# rpi-cc2652p-uart.net
KiCad netlist of a schematic drawn in EAGLE
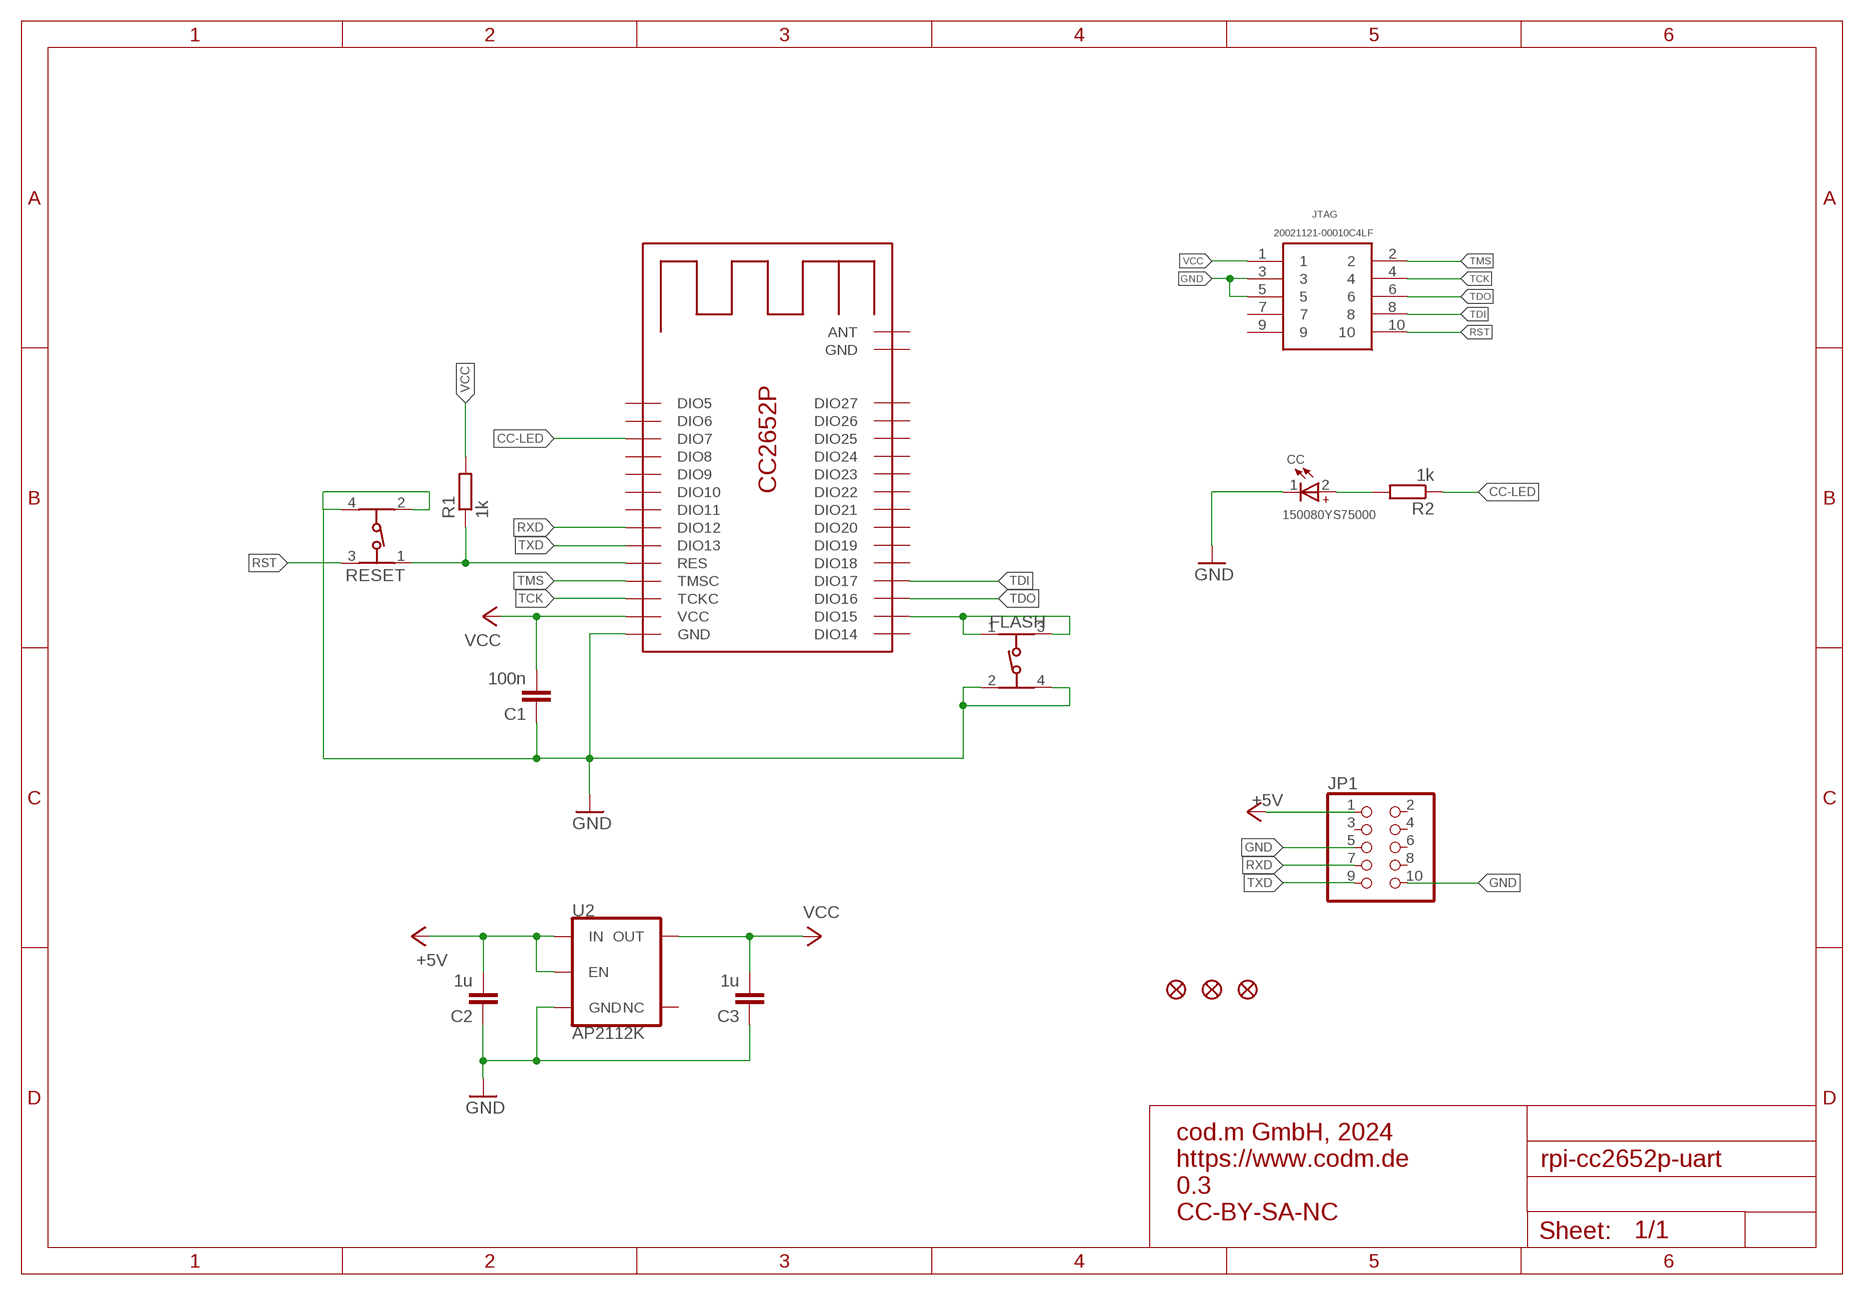
[diagram p0: schematic, sheet 1]

(export (version "E")
  (design (tool "Eeschema 10.0.6"))
  (components
    (comp (ref "C1")
      (value "100n")
      (footprint "eagle-import:C0603K")
      (libsource (lib "eagle-import") (part "C-EUC0603K"))
    )
    (comp (ref "C2")
      (value "1u")
      (footprint "eagle-import:C0805")
      (libsource (lib "eagle-import") (part "C-EUC0805"))
    )
    (comp (ref "C3")
      (value "1u")
      (footprint "eagle-import:C0805")
      (libsource (lib "eagle-import") (part "C-EUC0805"))
    )
    (comp (ref "CC")
      (value "150080YS75000")
      (footprint "eagle-import:WL-SMCW_0805")
      (libsource (lib "eagle-import") (part "WL-SMCW_0805_150080YS75000"))
    )
    (comp (ref "FD1")
      (value "FIDUCIAL1X2")
      (footprint "eagle-import:FIDUCIAL-1X2")
      (libsource (lib "eagle-import") (part "FIDUCIAL1X2"))
    )
    (comp (ref "FD2")
      (value "FIDUCIAL1X2")
      (footprint "eagle-import:FIDUCIAL-1X2")
      (libsource (lib "eagle-import") (part "FIDUCIAL1X2"))
    )
    (comp (ref "FD3")
      (value "FIDUCIAL1X2")
      (footprint "eagle-import:FIDUCIAL-1X2")
      (libsource (lib "eagle-import") (part "FIDUCIAL1X2"))
    )
    (comp (ref "FLASH")
      (value "434153017835")
      (footprint "eagle-import:434153017835")
      (libsource (lib "eagle-import") (part "434153017835"))
    )
    (comp (ref "JP1")
      (value "PINHD-2X5")
      (footprint "eagle-import:2X05")
      (libsource (lib "eagle-import") (part "PINHD-2X5"))
    )
    (comp (ref "JTAG")
      (value "20021121-00010C4LF")
      (footprint "eagle-import:2002112100010C4LF")
      (fields (field (name "MOUSER_PART_NUMBER") "649-202112100010C4LF"))
      (libsource (lib "eagle-import") (part "20021121-00010C4LF"))
    )
    (comp (ref "R1")
      (value "1k")
      (footprint "eagle-import:R0603RF")
      (libsource (lib "eagle-import") (part "R-EU_R0603RF"))
    )
    (comp (ref "R2")
      (value "1k")
      (footprint "eagle-import:R0603RF")
      (libsource (lib "eagle-import") (part "R-EU_R0603RF"))
    )
    (comp (ref "RESET")
      (value "434153017835")
      (footprint "eagle-import:434153017835")
      (libsource (lib "eagle-import") (part "434153017835"))
    )
    (comp (ref "U1")
      (value "CC2652P2-DUOWEISI")
      (footprint "eagle-import:CC2652P2-DUOWEISI")
      (libsource (lib "eagle-import") (part "CC2652P2-DUOWEISI"))
    )
    (comp (ref "U2")
      (value "AP2112K")
      (footprint "eagle-import:SOT23-5")
      (libsource (lib "eagle-import") (part "V_REG_AP2112K-3.3V"))
    )
  )
  (nets
    (net (code "1") (name "+5V") (class "Default")
      (node (ref "C2") (pin "2") (pinfunction "2_2") (pintype "passive"))
      (node (ref "JP1") (pin "1") (pinfunction "1_1") (pintype "passive"))
      (node (ref "U2") (pin "1") (pinfunction "IN_1") (pintype "input"))
      (node (ref "U2") (pin "3") (pinfunction "EN_3") (pintype "input"))
    )
    (net (code "2") (name "CC-LED") (class "Default")
      (node (ref "R2") (pin "1") (pinfunction "1_1") (pintype "passive"))
      (node (ref "U1") (pin "DIO7") (pinfunction "DIO7_DIO7") (pintype "bidirectional"))
    )
    (net (code "3") (name "GND") (class "Default")
      (node (ref "C1") (pin "1") (pinfunction "1_1") (pintype "passive"))
      (node (ref "C2") (pin "1") (pinfunction "1_1") (pintype "passive"))
      (node (ref "C3") (pin "1") (pinfunction "1_1") (pintype "passive"))
      (node (ref "CC") (pin "1") (pinfunction "-_1") (pintype "passive"))
      (node (ref "FLASH") (pin "2") (pinfunction "3_2") (pintype "passive"))
      (node (ref "FLASH") (pin "4") (pinfunction "4_4") (pintype "passive"))
      (node (ref "JP1") (pin "10") (pinfunction "10_10") (pintype "passive"))
      (node (ref "JP1") (pin "5") (pinfunction "5_5") (pintype "passive"))
      (node (ref "JTAG") (pin "3") (pinfunction "3_3") (pintype "bidirectional"))
      (node (ref "JTAG") (pin "5") (pinfunction "5_5") (pintype "bidirectional"))
      (node (ref "RESET") (pin "2") (pinfunction "3_2") (pintype "passive"))
      (node (ref "RESET") (pin "4") (pinfunction "4_4") (pintype "passive"))
      (node (ref "U1") (pin "GND") (pinfunction "GND_GND") (pintype "bidirectional"))
      (node (ref "U2") (pin "2") (pinfunction "GND_2") (pintype "input"))
    )
    (net (code "4") (name "Net-(CC-+)") (class "Default")
      (node (ref "CC") (pin "2") (pinfunction "+_2") (pintype "passive"))
      (node (ref "R2") (pin "2") (pinfunction "2_2") (pintype "passive"))
    )
    (net (code "5") (name "Net-(FLASH-2)") (class "Default")
      (node (ref "FLASH") (pin "1") (pinfunction "1_1") (pintype "passive"))
      (node (ref "FLASH") (pin "3") (pinfunction "2_3") (pintype "passive"))
      (node (ref "U1") (pin "DIO15") (pinfunction "DIO15_DIO15") (pintype "bidirectional"))
    )
    (net (code "6") (name "RST") (class "Default")
      (node (ref "JTAG") (pin "10") (pinfunction "10_10") (pintype "bidirectional"))
      (node (ref "R1") (pin "1") (pinfunction "1_1") (pintype "passive"))
      (node (ref "RESET") (pin "1") (pinfunction "1_1") (pintype "passive"))
      (node (ref "RESET") (pin "3") (pinfunction "2_3") (pintype "passive"))
      (node (ref "U1") (pin "RES") (pinfunction "RES_RES") (pintype "bidirectional"))
    )
    (net (code "7") (name "RXD") (class "Default")
      (node (ref "JP1") (pin "7") (pinfunction "7_7") (pintype "passive"))
      (node (ref "U1") (pin "DIO12") (pinfunction "DIO12_DIO12") (pintype "bidirectional"))
    )
    (net (code "8") (name "TCK") (class "Default")
      (node (ref "JTAG") (pin "4") (pinfunction "4_4") (pintype "bidirectional"))
      (node (ref "U1") (pin "TCKC") (pinfunction "TCKC_TCKC") (pintype "bidirectional"))
    )
    (net (code "9") (name "TDI") (class "Default")
      (node (ref "JTAG") (pin "8") (pinfunction "8_8") (pintype "bidirectional"))
      (node (ref "U1") (pin "DIO17") (pinfunction "DIO17_DIO17") (pintype "bidirectional"))
    )
    (net (code "10") (name "TDO") (class "Default")
      (node (ref "JTAG") (pin "6") (pinfunction "6_6") (pintype "bidirectional"))
      (node (ref "U1") (pin "DIO16") (pinfunction "DIO16_DIO16") (pintype "bidirectional"))
    )
    (net (code "11") (name "TMS") (class "Default")
      (node (ref "JTAG") (pin "2") (pinfunction "2_2") (pintype "bidirectional"))
      (node (ref "U1") (pin "TMSC") (pinfunction "TMSC_TMSC") (pintype "bidirectional"))
    )
    (net (code "12") (name "TXD") (class "Default")
      (node (ref "JP1") (pin "9") (pinfunction "9_9") (pintype "passive"))
      (node (ref "U1") (pin "DIO13") (pinfunction "DIO13_DIO13") (pintype "bidirectional"))
    )
    (net (code "13") (name "VCC") (class "Default")
      (node (ref "C1") (pin "2") (pinfunction "2_2") (pintype "passive"))
      (node (ref "C3") (pin "2") (pinfunction "2_2") (pintype "passive"))
      (node (ref "JTAG") (pin "1") (pinfunction "1_1") (pintype "bidirectional"))
      (node (ref "R1") (pin "2") (pinfunction "2_2") (pintype "passive"))
      (node (ref "U1") (pin "VCC") (pinfunction "VCC_VCC") (pintype "bidirectional"))
      (node (ref "U2") (pin "5") (pinfunction "OUT_5") (pintype "passive"))
    )
    (net (code "14") (name "unconnected-(JP1-Pad2)") (class "Default")
      (node (ref "JP1") (pin "2") (pinfunction "2_2") (pintype "passive"))
    )
    (net (code "15") (name "unconnected-(JP1-Pad3)") (class "Default")
      (node (ref "JP1") (pin "3") (pinfunction "3_3") (pintype "passive"))
    )
    (net (code "16") (name "unconnected-(JP1-Pad4)") (class "Default")
      (node (ref "JP1") (pin "4") (pinfunction "4_4") (pintype "passive"))
    )
    (net (code "17") (name "unconnected-(JP1-Pad6)") (class "Default")
      (node (ref "JP1") (pin "6") (pinfunction "6_6") (pintype "passive"))
    )
    (net (code "18") (name "unconnected-(JP1-Pad8)") (class "Default")
      (node (ref "JP1") (pin "8") (pinfunction "8_8") (pintype "passive"))
    )
    (net (code "19") (name "unconnected-(JTAG-Pad7)") (class "Default")
      (node (ref "JTAG") (pin "7") (pinfunction "7_7") (pintype "bidirectional"))
    )
    (net (code "20") (name "unconnected-(JTAG-Pad9)") (class "Default")
      (node (ref "JTAG") (pin "9") (pinfunction "9_9") (pintype "bidirectional"))
    )
    (net (code "21") (name "unconnected-(U1-GND-PadGND@1)") (class "Default")
      (node (ref "U1") (pin "GND@1") (pinfunction "GND_GND@1") (pintype "bidirectional"))
    )
    (net (code "22") (name "unconnected-(U1-PadANT)") (class "Default")
      (node (ref "U1") (pin "ANT") (pinfunction "ANT_ANT") (pintype "bidirectional"))
    )
    (net (code "23") (name "unconnected-(U1-PadDIO5)") (class "Default")
      (node (ref "U1") (pin "DIO5") (pinfunction "DIO5_DIO5") (pintype "bidirectional"))
    )
    (net (code "24") (name "unconnected-(U1-PadDIO6)") (class "Default")
      (node (ref "U1") (pin "DIO6") (pinfunction "DIO6_DIO6") (pintype "bidirectional"))
    )
    (net (code "25") (name "unconnected-(U1-PadDIO8)") (class "Default")
      (node (ref "U1") (pin "DIO8") (pinfunction "DIO8_DIO8") (pintype "bidirectional"))
    )
    (net (code "26") (name "unconnected-(U1-PadDIO9)") (class "Default")
      (node (ref "U1") (pin "DIO9") (pinfunction "DIO9_DIO9") (pintype "bidirectional"))
    )
    (net (code "27") (name "unconnected-(U1-PadDIO10)") (class "Default")
      (node (ref "U1") (pin "DIO10") (pinfunction "DIO10_DIO10") (pintype "bidirectional"))
    )
    (net (code "28") (name "unconnected-(U1-PadDIO11)") (class "Default")
      (node (ref "U1") (pin "DIO11") (pinfunction "DIO11_DIO11") (pintype "bidirectional"))
    )
    (net (code "29") (name "unconnected-(U1-PadDIO14)") (class "Default")
      (node (ref "U1") (pin "DIO14") (pinfunction "DIO14_DIO14") (pintype "bidirectional"))
    )
    (net (code "30") (name "unconnected-(U1-PadDIO18)") (class "Default")
      (node (ref "U1") (pin "DIO18") (pinfunction "DIO18_DIO18") (pintype "bidirectional"))
    )
    (net (code "31") (name "unconnected-(U1-PadDIO19)") (class "Default")
      (node (ref "U1") (pin "DIO19") (pinfunction "DIO19_DIO19") (pintype "bidirectional"))
    )
    (net (code "32") (name "unconnected-(U1-PadDIO20)") (class "Default")
      (node (ref "U1") (pin "DIO20") (pinfunction "DIO20_DIO20") (pintype "bidirectional"))
    )
    (net (code "33") (name "unconnected-(U1-PadDIO21)") (class "Default")
      (node (ref "U1") (pin "DIO21") (pinfunction "DIO21_DIO21") (pintype "bidirectional"))
    )
    (net (code "34") (name "unconnected-(U1-PadDIO22)") (class "Default")
      (node (ref "U1") (pin "DIO22") (pinfunction "DIO22_DIO22") (pintype "bidirectional"))
    )
    (net (code "35") (name "unconnected-(U1-PadDIO23)") (class "Default")
      (node (ref "U1") (pin "DIO23") (pinfunction "DIO23_DIO23") (pintype "bidirectional"))
    )
    (net (code "36") (name "unconnected-(U1-PadDIO24)") (class "Default")
      (node (ref "U1") (pin "DIO24") (pinfunction "DIO24_DIO24") (pintype "bidirectional"))
    )
    (net (code "37") (name "unconnected-(U1-PadDIO25)") (class "Default")
      (node (ref "U1") (pin "DIO25") (pinfunction "DIO25_DIO25") (pintype "bidirectional"))
    )
    (net (code "38") (name "unconnected-(U1-PadDIO26)") (class "Default")
      (node (ref "U1") (pin "DIO26") (pinfunction "DIO26_DIO26") (pintype "bidirectional"))
    )
    (net (code "39") (name "unconnected-(U1-PadDIO27)") (class "Default")
      (node (ref "U1") (pin "DIO27") (pinfunction "DIO27_DIO27") (pintype "bidirectional"))
    )
    (net (code "40") (name "unconnected-(U2-NC-Pad4)") (class "Default")
      (node (ref "U2") (pin "4") (pinfunction "NC_4") (pintype "no_connect"))
    )
  )
)
